# 14_IO_MIPI.net
KiCad netlist of a schematic drawn in Altium Designer
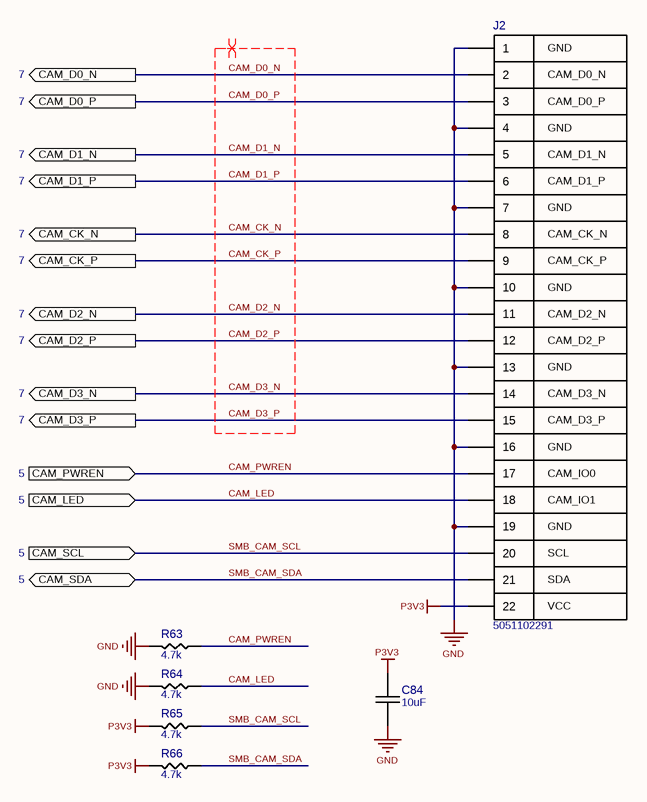
[diagram p0: 14_IO_MIPI.SchDoc]

(export (version "E")
  (design (tool "Eeschema 10.0.6"))
  (components
    (comp (ref "C84")
      (value "10uF")
      (footprint "CAPC1005X06N")
      (description "CAP CER 10UF 6.3V X5R 0402")
      (fields (field (name "PART NUMBER") "GRM155R60J106ME47D") (field (name "VOLTAGE") "6.3V"))
      (libsource (lib "Database") (part "Capacitor"))
    )
    (comp (ref "J2")
      (value "5051102291")
      (footprint "MOLEX_5051102291")
      (description "CONN FFC/FPC BOTTOM 22P .5MM R/A")
      (libsource (lib "Database") (part "Connector P22"))
    )
    (comp (ref "R63")
      (value "4.7k")
      (footprint "RESC1005X03N")
      (description "RES SMD 4.7K OHM 1% 1/16W 0402")
      (fields (field (name "PART NUMBER") "RC0402FR-074K7L"))
      (libsource (lib "Database") (part "Resistor_ENG"))
    )
    (comp (ref "R64")
      (value "4.7k")
      (footprint "RESC1005X03N")
      (description "RES SMD 4.7K OHM 1% 1/16W 0402")
      (fields (field (name "PART NUMBER") "RC0402FR-074K7L"))
      (libsource (lib "Database") (part "Resistor_ENG"))
    )
    (comp (ref "R65")
      (value "4.7k")
      (footprint "RESC1005X03N")
      (description "RES SMD 4.7K OHM 1% 1/16W 0402")
      (fields (field (name "PART NUMBER") "RC0402FR-074K7L"))
      (libsource (lib "Database") (part "Resistor_ENG"))
    )
    (comp (ref "R66")
      (value "4.7k")
      (footprint "RESC1005X03N")
      (description "RES SMD 4.7K OHM 1% 1/16W 0402")
      (fields (field (name "PART NUMBER") "RC0402FR-074K7L"))
      (libsource (lib "Database") (part "Resistor_ENG"))
    )
  )
  (nets
    (net (code "1") (name "/CAM_CK_N") (class "Default")
      (node (ref "J2") (pin "8") (pinfunction "8_8") (pintype "passive"))
    )
    (net (code "2") (name "/CAM_CK_P") (class "Default")
      (node (ref "J2") (pin "9") (pinfunction "9_9") (pintype "passive"))
    )
    (net (code "3") (name "/CAM_D0_N") (class "Default")
      (node (ref "J2") (pin "2") (pinfunction "2_2") (pintype "passive"))
    )
    (net (code "4") (name "/CAM_D0_P") (class "Default")
      (node (ref "J2") (pin "3") (pinfunction "3_3") (pintype "passive"))
    )
    (net (code "5") (name "/CAM_D1_N") (class "Default")
      (node (ref "J2") (pin "5") (pinfunction "5_5") (pintype "passive"))
    )
    (net (code "6") (name "/CAM_D1_P") (class "Default")
      (node (ref "J2") (pin "6") (pinfunction "6_6") (pintype "passive"))
    )
    (net (code "7") (name "/CAM_D2_N") (class "Default")
      (node (ref "J2") (pin "11") (pinfunction "11_11") (pintype "passive"))
    )
    (net (code "8") (name "/CAM_D2_P") (class "Default")
      (node (ref "J2") (pin "12") (pinfunction "12_12") (pintype "passive"))
    )
    (net (code "9") (name "/CAM_D3_N") (class "Default")
      (node (ref "J2") (pin "14") (pinfunction "14_14") (pintype "passive"))
    )
    (net (code "10") (name "/CAM_D3_P") (class "Default")
      (node (ref "J2") (pin "15") (pinfunction "15_15") (pintype "passive"))
    )
    (net (code "11") (name "/CAM_LED") (class "Default")
      (node (ref "J2") (pin "18") (pinfunction "18_18") (pintype "passive"))
      (node (ref "R64") (pin "1") (pinfunction "1_1") (pintype "passive"))
    )
    (net (code "12") (name "/CAM_PWREN") (class "Default")
      (node (ref "J2") (pin "17") (pinfunction "17_17") (pintype "passive"))
      (node (ref "R63") (pin "1") (pinfunction "1_1") (pintype "passive"))
    )
    (net (code "13") (name "/SMB_CAM_SCL") (class "Default")
      (node (ref "J2") (pin "20") (pinfunction "20_20") (pintype "passive"))
      (node (ref "R65") (pin "1") (pinfunction "1_1") (pintype "passive"))
    )
    (net (code "14") (name "/SMB_CAM_SDA") (class "Default")
      (node (ref "J2") (pin "21") (pinfunction "21_21") (pintype "passive"))
      (node (ref "R66") (pin "1") (pinfunction "1_1") (pintype "passive"))
    )
    (net (code "15") (name "GND") (class "Default")
      (node (ref "C84") (pin "1") (pinfunction "1_1") (pintype "passive"))
      (node (ref "J2") (pin "1") (pinfunction "1_1") (pintype "passive"))
      (node (ref "J2") (pin "10") (pinfunction "10_10") (pintype "passive"))
      (node (ref "J2") (pin "13") (pinfunction "13_13") (pintype "passive"))
      (node (ref "J2") (pin "16") (pinfunction "16_16") (pintype "passive"))
      (node (ref "J2") (pin "19") (pinfunction "19_19") (pintype "passive"))
      (node (ref "J2") (pin "4") (pinfunction "4_4") (pintype "passive"))
      (node (ref "J2") (pin "7") (pinfunction "7_7") (pintype "passive"))
      (node (ref "R63") (pin "2") (pinfunction "2_2") (pintype "passive"))
      (node (ref "R64") (pin "2") (pinfunction "2_2") (pintype "passive"))
    )
    (net (code "16") (name "P3V3") (class "Default")
      (node (ref "C84") (pin "2") (pinfunction "2_2") (pintype "passive"))
      (node (ref "J2") (pin "22") (pinfunction "22_22") (pintype "passive"))
      (node (ref "R65") (pin "2") (pinfunction "2_2") (pintype "passive"))
      (node (ref "R66") (pin "2") (pinfunction "2_2") (pintype "passive"))
    )
  )
)
